# HeatPlatform_V1_1.net
KiCad netlist of a schematic drawn in Altium Designer
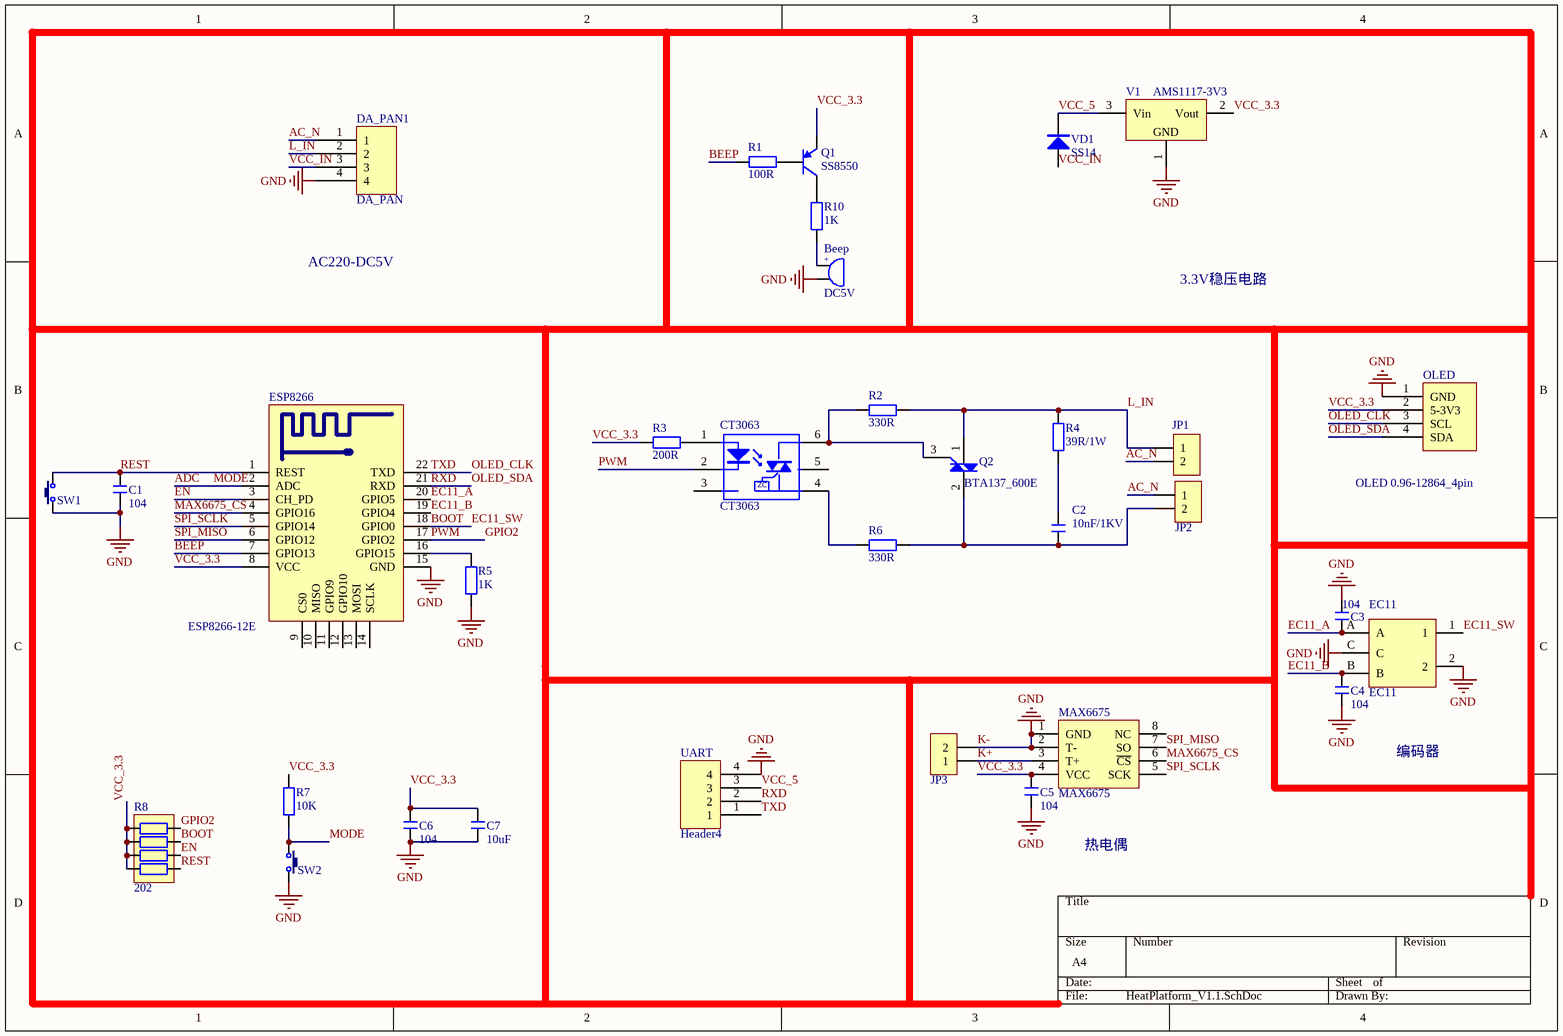
[diagram p0: HeatPlatform_V1.1.SchDoc]

(export (version "E")
  (design (tool "Eeschema 10.0.6"))
  (components
    (comp (ref "Beep")
      (value "DC5V")
      (footprint "BEEP 5x9x5.5")
      (description "蜂鸣器")
      (fields (field (name "版权归属") "源创客"))
      (libsource (lib "HeatPlatform") (part "BEEP"))
    )
    (comp (ref "C1")
      (value "104")
      (footprint "C 0603")
      (description "无极性贴片电容")
      (fields (field (name "版权归属") "源创客"))
      (libsource (lib "HeatPlatform") (part "C"))
    )
    (comp (ref "C2")
      (value "10nF/1KV")
      (footprint "C 1210_L")
      (description "无极性贴片电容")
      (fields (field (name "版权归属") "源创客"))
      (libsource (lib "HeatPlatform") (part "C"))
    )
    (comp (ref "C3")
      (value "104")
      (footprint "C 0603")
      (description "无极性贴片电容")
      (fields (field (name "版权归属") "源创客"))
      (libsource (lib "HeatPlatform") (part "C"))
    )
    (comp (ref "C4")
      (value "104")
      (footprint "C 0603")
      (description "无极性贴片电容")
      (fields (field (name "版权归属") "源创客"))
      (libsource (lib "HeatPlatform") (part "C"))
    )
    (comp (ref "C5")
      (value "104")
      (footprint "C 0603")
      (description "无极性贴片电容")
      (fields (field (name "版权归属") "源创客"))
      (libsource (lib "HeatPlatform") (part "C"))
    )
    (comp (ref "C6")
      (value "104")
      (footprint "C 0603")
      (description "无极性贴片电容")
      (fields (field (name "版权归属") "源创客"))
      (libsource (lib "HeatPlatform") (part "C"))
    )
    (comp (ref "C7")
      (value "10uF")
      (footprint "C 0603")
      (description "无极性贴片电容")
      (fields (field (name "版权归属") "源创客"))
      (libsource (lib "HeatPlatform") (part "C"))
    )
    (comp (ref "CT3063")
      (value "CT3063")
      (footprint "SMD-6")
      (description "线性光耦（过零检测）")
      (fields (field (name "版权归属") "源创客"))
      (libsource (lib "HeatPlatform") (part "CT3063"))
    )
    (comp (ref "DA_PAN1")
      (value "DA_PAN")
      (footprint "DA_PAN")
      (libsource (lib "HeatPlatform") (part "DA_PAN"))
    )
    (comp (ref "EC11")
      (value "EC11")
      (footprint "EC11")
      (description "数字开关编码器")
      (fields (field (name "版权归属") "源创客"))
      (libsource (lib "HeatPlatform") (part "EC11"))
    )
    (comp (ref "ESP8266")
      (value "ESP8266-12E")
      (footprint "ESP_12E")
      (description "串口 WIFI模块，ESP-12E")
      (fields (field (name "版权归属") "源创客"))
      (libsource (lib "HeatPlatform") (part "ESP8266-12E"))
    )
    (comp (ref "JP1")
      (value "HDR-1X2")
      (footprint "HDR-1X2")
      (description "2P接插件")
      (fields (field (name "版权归属") "源创客"))
      (libsource (lib "HeatPlatform") (part "Header 2"))
    )
    (comp (ref "JP2")
      (value "HDR-1X2")
      (footprint "HDR-1X2")
      (description "2P接插件")
      (fields (field (name "版权归属") "源创客"))
      (libsource (lib "HeatPlatform") (part "Header 2"))
    )
    (comp (ref "JP3")
      (value "HDR-1X2")
      (footprint "HDR-1X2")
      (description "2P接插件")
      (fields (field (name "版权归属") "源创客"))
      (libsource (lib "") (part "Header 2_1"))
    )
    (comp (ref "MAX6675")
      (value "MAX6675")
      (footprint "SOP8_L")
      (description "K型热电偶检测芯片")
      (fields (field (name "版权归属") "源创客"))
      (libsource (lib "HeatPlatform") (part "MAX6675"))
    )
    (comp (ref "OLED")
      (value "OLED 0.96-12864_4pin")
      (footprint "OLED 0.96-12864_4pin")
      (description "12864 点阵屏")
      (libsource (lib "HeatPlatform") (part "OLED 0.96-12864_4pin"))
    )
    (comp (ref "Q1")
      (value "SS8550")
      (footprint "SOT23-3L")
      (description "高频放大-PNP型")
      (fields (field (name "版权归属") "源创客"))
      (libsource (lib "HeatPlatform") (part "8550-SMD"))
    )
    (comp (ref "Q2")
      (value "BTA137_600E")
      (footprint "TO252")
      (description "双向可控硅")
      (fields (field (name "版权归属") "源创客"))
      (libsource (lib "HeatPlatform") (part "BTA12_600"))
    )
    (comp (ref "R1")
      (value "100R")
      (footprint "R 0603")
      (description "贴片电阻")
      (fields (field (name "版权归属") "源创客"))
      (libsource (lib "HeatPlatform") (part "R"))
    )
    (comp (ref "R2")
      (value "330R")
      (footprint "R 0603")
      (description "贴片电阻")
      (fields (field (name "版权归属") "源创客"))
      (libsource (lib "HeatPlatform") (part "R"))
    )
    (comp (ref "R3")
      (value "200R")
      (footprint "R 0603")
      (description "贴片电阻")
      (fields (field (name "版权归属") "源创客"))
      (libsource (lib "HeatPlatform") (part "R"))
    )
    (comp (ref "R4")
      (value "39R/1W")
      (footprint "R 2512_L")
      (description "贴片电阻")
      (fields (field (name "版权归属") "源创客"))
      (libsource (lib "HeatPlatform") (part "R"))
    )
    (comp (ref "R5")
      (value "1K")
      (footprint "R 0603")
      (description "贴片电阻")
      (fields (field (name "版权归属") "源创客"))
      (libsource (lib "HeatPlatform") (part "R"))
    )
    (comp (ref "R6")
      (value "330R")
      (footprint "R 0603")
      (description "贴片电阻")
      (fields (field (name "版权归属") "源创客"))
      (libsource (lib "HeatPlatform") (part "R"))
    )
    (comp (ref "R7")
      (value "10K")
      (footprint "R 0603")
      (description "贴片电阻")
      (fields (field (name "版权归属") "源创客"))
      (libsource (lib "HeatPlatform") (part "R"))
    )
    (comp (ref "R8")
      (value "202")
      (footprint "RCA-8P4R-0603")
      (description "贴片网络排阻")
      (fields (field (name "版权归属") "源创客"))
      (libsource (lib "HeatPlatform") (part "R-8P4R"))
    )
    (comp (ref "R10")
      (value "1K")
      (footprint "R 0603")
      (description "贴片电阻")
      (fields (field (name "版权归属") "源创客"))
      (libsource (lib "HeatPlatform") (part "R"))
    )
    (comp (ref "SW1")
      (value "3*4*2")
      (footprint "TSW SMD-3*4*2")
      (description "3x4轻触开关")
      (fields (field (name "版权归属") "源创客"))
      (libsource (lib "") (part "TSW 3x4_1"))
    )
    (comp (ref "SW2")
      (value "3*4*2")
      (footprint "TSW SMD-3*4*2")
      (description "3x4轻触开关")
      (fields (field (name "版权归属") "源创客"))
      (libsource (lib "HeatPlatform") (part "TSW 3x4"))
    )
    (comp (ref "UART")
      (value "Header4")
      (footprint "HDR2.54-LI-4P")
      (libsource (lib "HeatPlatform") (part "Header4"))
    )
    (comp (ref "V1")
      (value "AMS1117-3V3")
      (footprint "SOT223_L")
      (description "三端稳压芯片")
      (fields (field (name "版权归属") "源创客"))
      (libsource (lib "HeatPlatform") (part "AMS1117"))
    )
    (comp (ref "VD1")
      (value "SS14")
      (footprint "SMA")
      (description "肖特基二极管")
      (fields (field (name "版权归属") "源创客"))
      (libsource (lib "HeatPlatform") (part "SS14"))
    )
  )
  (nets
    (net (code "1") (name "/AC_N") (class "Default")
      (node (ref "DA_PAN1") (pin "1") (pinfunction "1_1") (pintype "passive"))
      (node (ref "JP1") (pin "2") (pinfunction "2_2") (pintype "passive"))
      (node (ref "JP2") (pin "1") (pinfunction "1_1") (pintype "passive"))
    )
    (net (code "2") (name "/ADC") (class "Default")
      (node (ref "ESP8266") (pin "2") (pinfunction "ADC_2") (pintype "passive"))
      (node (ref "R7") (pin "1") (pinfunction "1_1") (pintype "passive"))
      (node (ref "SW2") (pin "1") (pinfunction "1_1") (pintype "passive"))
    )
    (net (code "3") (name "/BEEP") (class "Default")
      (node (ref "ESP8266") (pin "7") (pinfunction "GPIO13_7") (pintype "passive"))
      (node (ref "R1") (pin "1") (pinfunction "1_1") (pintype "passive"))
    )
    (net (code "4") (name "/BOOT") (class "Default")
      (node (ref "EC11") (pin "1") (pinfunction "1_1") (pintype "passive"))
      (node (ref "ESP8266") (pin "18") (pinfunction "GPIO0_18") (pintype "passive"))
      (node (ref "R8") (pin "7") (pinfunction "7_7") (pintype "passive"))
    )
    (net (code "5") (name "/EC11_A") (class "Default")
      (node (ref "C3") (pin "1") (pinfunction "1_1") (pintype "passive"))
      (node (ref "EC11") (pin "A") (pinfunction "A_A") (pintype "passive"))
      (node (ref "ESP8266") (pin "20") (pinfunction "GPIO5_20") (pintype "passive"))
    )
    (net (code "6") (name "/EC11_B") (class "Default")
      (node (ref "C4") (pin "2") (pinfunction "2_2") (pintype "passive"))
      (node (ref "EC11") (pin "B") (pinfunction "B_B") (pintype "passive"))
      (node (ref "ESP8266") (pin "19") (pinfunction "GPIO4_19") (pintype "passive"))
    )
    (net (code "7") (name "/EN") (class "Default")
      (node (ref "ESP8266") (pin "3") (pinfunction "CH_PD_3") (pintype "passive"))
      (node (ref "R8") (pin "6") (pinfunction "6_6") (pintype "passive"))
    )
    (net (code "8") (name "/GPIO2") (class "Default")
      (node (ref "CT3063") (pin "2") (pinfunction "C_2") (pintype "passive"))
      (node (ref "ESP8266") (pin "17") (pinfunction "GPIO2_17") (pintype "passive"))
      (node (ref "R8") (pin "8") (pinfunction "8_8") (pintype "passive"))
    )
    (net (code "9") (name "/K+") (class "Default")
      (node (ref "JP3") (pin "1") (pinfunction "1_1") (pintype "passive"))
      (node (ref "MAX6675") (pin "3") (pinfunction "T+_3") (pintype "passive"))
    )
    (net (code "10") (name "/L_IN") (class "Default")
      (node (ref "DA_PAN1") (pin "2") (pinfunction "2_2") (pintype "passive"))
      (node (ref "JP1") (pin "1") (pinfunction "1_1") (pintype "passive"))
      (node (ref "Q2") (pin "1") (pinfunction "A1_1") (pintype "passive"))
      (node (ref "R2") (pin "2") (pinfunction "2_2") (pintype "passive"))
      (node (ref "R4") (pin "2") (pinfunction "2_2") (pintype "passive"))
    )
    (net (code "11") (name "/MAX6675_CS") (class "Default")
      (node (ref "ESP8266") (pin "4") (pinfunction "GPIO16_4") (pintype "passive"))
      (node (ref "MAX6675") (pin "6") (pinfunction "~{CS}_6") (pintype "passive"))
    )
    (net (code "12") (name "/OLED_CLK") (class "Default")
      (node (ref "ESP8266") (pin "22") (pinfunction "TXD_22") (pintype "passive"))
      (node (ref "OLED") (pin "3") (pinfunction "SCL_3") (pintype "passive"))
      (node (ref "UART") (pin "1") (pinfunction "1_1") (pintype "passive"))
    )
    (net (code "13") (name "/OLED_SDA") (class "Default")
      (node (ref "ESP8266") (pin "21") (pinfunction "RXD_21") (pintype "passive"))
      (node (ref "OLED") (pin "4") (pinfunction "SDA_4") (pintype "passive"))
      (node (ref "UART") (pin "2") (pinfunction "2_2") (pintype "passive"))
    )
    (net (code "14") (name "/REST") (class "Default")
      (node (ref "C1") (pin "2") (pinfunction "2_2") (pintype "passive"))
      (node (ref "ESP8266") (pin "1") (pinfunction "REST_1") (pintype "passive"))
      (node (ref "R8") (pin "5") (pinfunction "5_5") (pintype "passive"))
      (node (ref "SW1") (pin "2") (pinfunction "2_2") (pintype "passive"))
    )
    (net (code "15") (name "/SPI_MISO") (class "Default")
      (node (ref "ESP8266") (pin "6") (pinfunction "GPIO12_6") (pintype "passive"))
      (node (ref "MAX6675") (pin "7") (pinfunction "SO_7") (pintype "passive"))
    )
    (net (code "16") (name "/SPI_SCLK") (class "Default")
      (node (ref "ESP8266") (pin "5") (pinfunction "GPIO14_5") (pintype "passive"))
      (node (ref "MAX6675") (pin "5") (pinfunction "SCK_5") (pintype "passive"))
    )
    (net (code "17") (name "/VCC_3.3") (class "Default")
      (node (ref "C5") (pin "2") (pinfunction "2_2") (pintype "passive"))
      (node (ref "C6") (pin "2") (pinfunction "2_2") (pintype "passive"))
      (node (ref "C7") (pin "2") (pinfunction "2_2") (pintype "passive"))
      (node (ref "ESP8266") (pin "8") (pinfunction "VCC_8") (pintype "passive"))
      (node (ref "MAX6675") (pin "4") (pinfunction "VCC_4") (pintype "passive"))
      (node (ref "OLED") (pin "2") (pinfunction "5-3V3_2") (pintype "passive"))
      (node (ref "Q1") (pin "2") (pinfunction "E_2") (pintype "passive"))
      (node (ref "R3") (pin "2") (pinfunction "2_2") (pintype "passive"))
      (node (ref "R7") (pin "2") (pinfunction "2_2") (pintype "passive"))
      (node (ref "R8") (pin "1") (pinfunction "1_1") (pintype "passive"))
      (node (ref "R8") (pin "2") (pinfunction "2_2") (pintype "passive"))
      (node (ref "R8") (pin "3") (pinfunction "3_3") (pintype "passive"))
      (node (ref "R8") (pin "4") (pinfunction "4_4") (pintype "passive"))
      (node (ref "V1") (pin "2") (pinfunction "Vout_2") (pintype "passive"))
    )
    (net (code "18") (name "/VCC_5") (class "Default")
      (node (ref "UART") (pin "3") (pinfunction "3_3") (pintype "passive"))
      (node (ref "V1") (pin "3") (pinfunction "Vin_3") (pintype "passive"))
      (node (ref "VD1") (pin "2") (pinfunction "K_2") (pintype "passive"))
    )
    (net (code "19") (name "/VCC_IN") (class "Default")
      (node (ref "DA_PAN1") (pin "3") (pinfunction "3_3") (pintype "passive"))
      (node (ref "VD1") (pin "1") (pinfunction "A_1") (pintype "passive"))
    )
    (net (code "20") (name "GND") (class "Default")
      (node (ref "Beep") (pin "2") (pinfunction "2_2") (pintype "passive"))
      (node (ref "C1") (pin "1") (pinfunction "1_1") (pintype "passive"))
      (node (ref "C3") (pin "2") (pinfunction "2_2") (pintype "passive"))
      (node (ref "C4") (pin "1") (pinfunction "1_1") (pintype "passive"))
      (node (ref "C5") (pin "1") (pinfunction "1_1") (pintype "passive"))
      (node (ref "C6") (pin "1") (pinfunction "1_1") (pintype "passive"))
      (node (ref "C7") (pin "1") (pinfunction "1_1") (pintype "passive"))
      (node (ref "DA_PAN1") (pin "4") (pinfunction "4_4") (pintype "passive"))
      (node (ref "EC11") (pin "2") (pinfunction "2_2") (pintype "passive"))
      (node (ref "EC11") (pin "C") (pinfunction "C_C") (pintype "passive"))
      (node (ref "ESP8266") (pin "15") (pinfunction "GND_15") (pintype "passive"))
      (node (ref "JP3") (pin "2") (pinfunction "2_2") (pintype "passive"))
      (node (ref "MAX6675") (pin "1") (pinfunction "GND_1") (pintype "passive"))
      (node (ref "MAX6675") (pin "2") (pinfunction "T-_2") (pintype "passive"))
      (node (ref "OLED") (pin "1") (pinfunction "GND_1") (pintype "passive"))
      (node (ref "R5") (pin "1") (pinfunction "1_1") (pintype "passive"))
      (node (ref "SW1") (pin "1") (pinfunction "1_1") (pintype "passive"))
      (node (ref "SW2") (pin "2") (pinfunction "2_2") (pintype "passive"))
      (node (ref "UART") (pin "4") (pinfunction "4_4") (pintype "passive"))
      (node (ref "V1") (pin "1") (pinfunction "GND_1") (pintype "passive"))
    )
    (net (code "21") (name "Net-(Beep-Pad1)") (class "Default")
      (node (ref "Beep") (pin "1") (pinfunction "1_1") (pintype "passive"))
      (node (ref "R10") (pin "1") (pinfunction "1_1") (pintype "passive"))
    )
    (net (code "22") (name "Net-(C2-Pad2)") (class "Default")
      (node (ref "C2") (pin "2") (pinfunction "2_2") (pintype "passive"))
      (node (ref "R4") (pin "1") (pinfunction "1_1") (pintype "passive"))
    )
    (net (code "23") (name "Net-(CT3063-A)") (class "Default")
      (node (ref "CT3063") (pin "1") (pinfunction "A_1") (pintype "passive"))
      (node (ref "R3") (pin "1") (pinfunction "1_1") (pintype "passive"))
    )
    (net (code "24") (name "Net-(CT3063-MT1)") (class "Default")
      (node (ref "CT3063") (pin "6") (pinfunction "MT1_6") (pintype "passive"))
      (node (ref "Q2") (pin "3") (pinfunction "G_3") (pintype "passive"))
      (node (ref "R2") (pin "1") (pinfunction "1_1") (pintype "passive"))
    )
    (net (code "25") (name "Net-(CT3063-MT2)") (class "Default")
      (node (ref "CT3063") (pin "4") (pinfunction "MT2_4") (pintype "passive"))
      (node (ref "R6") (pin "2") (pinfunction "2_2") (pintype "passive"))
    )
    (net (code "26") (name "Net-(ESP8266-GPIO15)") (class "Default")
      (node (ref "ESP8266") (pin "16") (pinfunction "GPIO15_16") (pintype "passive"))
      (node (ref "R5") (pin "2") (pinfunction "2_2") (pintype "passive"))
    )
    (net (code "27") (name "Net-(Q1-B)") (class "Default")
      (node (ref "Q1") (pin "1") (pinfunction "B_1") (pintype "passive"))
      (node (ref "R1") (pin "2") (pinfunction "2_2") (pintype "passive"))
    )
    (net (code "28") (name "Net-(Q1-C)") (class "Default")
      (node (ref "Q1") (pin "3") (pinfunction "C_3") (pintype "passive"))
      (node (ref "R10") (pin "2") (pinfunction "2_2") (pintype "passive"))
    )
    (net (code "29") (name "Net-(Q2-A2)") (class "Default")
      (node (ref "C2") (pin "1") (pinfunction "1_1") (pintype "passive"))
      (node (ref "JP2") (pin "2") (pinfunction "2_2") (pintype "passive"))
      (node (ref "Q2") (pin "2") (pinfunction "A2_2") (pintype "passive"))
      (node (ref "R6") (pin "1") (pinfunction "1_1") (pintype "passive"))
    )
    (net (code "30") (name "unconnected-(CT3063-NC-Pad3)") (class "Default")
      (node (ref "CT3063") (pin "3") (pinfunction "NC_3") (pintype "passive"))
    )
    (net (code "31") (name "unconnected-(CT3063-NC-Pad5)") (class "Default")
      (node (ref "CT3063") (pin "5") (pinfunction "NC_5") (pintype "passive"))
    )
    (net (code "32") (name "unconnected-(ESP8266-CS0-Pad9)") (class "Default")
      (node (ref "ESP8266") (pin "9") (pinfunction "CS0_9") (pintype "passive"))
    )
    (net (code "33") (name "unconnected-(ESP8266-GPIO9-Pad11)") (class "Default")
      (node (ref "ESP8266") (pin "11") (pinfunction "GPIO9_11") (pintype "passive"))
    )
    (net (code "34") (name "unconnected-(ESP8266-GPIO10-Pad12)") (class "Default")
      (node (ref "ESP8266") (pin "12") (pinfunction "GPIO10_12") (pintype "passive"))
    )
    (net (code "35") (name "unconnected-(ESP8266-MISO-Pad10)") (class "Default")
      (node (ref "ESP8266") (pin "10") (pinfunction "MISO_10") (pintype "passive"))
    )
    (net (code "36") (name "unconnected-(ESP8266-MOSI-Pad13)") (class "Default")
      (node (ref "ESP8266") (pin "13") (pinfunction "MOSI_13") (pintype "passive"))
    )
    (net (code "37") (name "unconnected-(ESP8266-SCLK-Pad14)") (class "Default")
      (node (ref "ESP8266") (pin "14") (pinfunction "SCLK_14") (pintype "passive"))
    )
    (net (code "38") (name "unconnected-(MAX6675-NC-Pad8)") (class "Default")
      (node (ref "MAX6675") (pin "8") (pinfunction "NC_8") (pintype "passive"))
    )
  )
)
